# 18F_Proto2.net
KiCad netlist of a schematic drawn in EAGLE
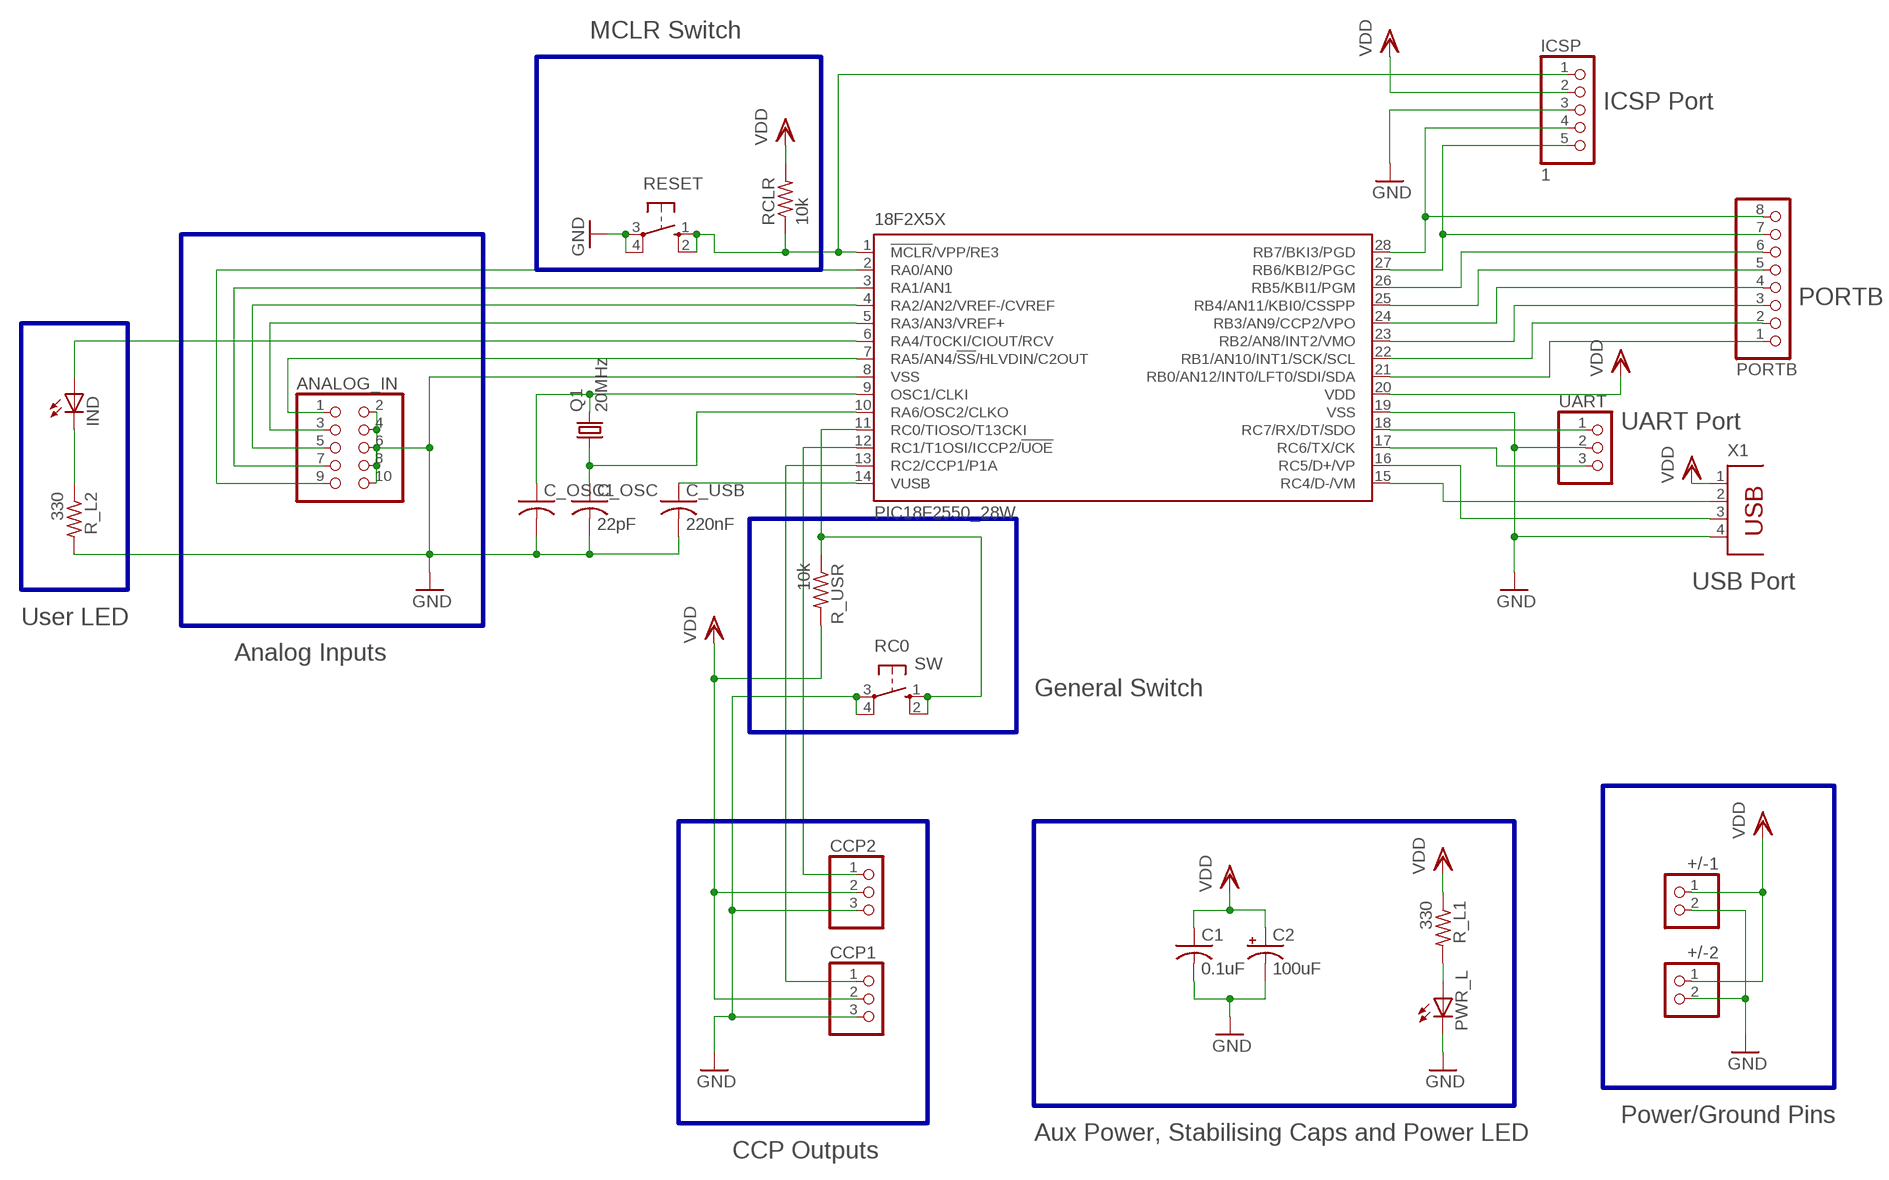
[diagram p0: schematic, sheet 1]

(export (version "E")
  (design (tool "Eeschema 10.0.6"))
  (components
    (comp (ref "+/-1")
      (value "PINHD-1X2")
      (footprint "eagle-import:1X02")
      (libsource (lib "eagle-import") (part "PINHD-1X2"))
    )
    (comp (ref "+/-2")
      (value "PINHD-1X2")
      (footprint "eagle-import:1X02")
      (libsource (lib "eagle-import") (part "PINHD-1X2"))
    )
    (comp (ref "18F2X5X")
      (value "PIC18F2550_28W")
      (footprint "eagle-import:SO28W")
      (fields (field (name "MF") "MICROCHIP") (field (name "MPN") "PIC18F2550-I/SO"))
      (libsource (lib "eagle-import") (part "PIC18F2_28W550"))
    )
    (comp (ref "ANALOG_IN")
      (value "PINHD-2X5")
      (footprint "eagle-import:2X05")
      (libsource (lib "eagle-import") (part "PINHD-2X5"))
    )
    (comp (ref "C1")
      (value "0.1uF")
      (footprint "eagle-import:C050-025X075")
      (libsource (lib "eagle-import") (part "C-US050-025X075"))
    )
    (comp (ref "C2")
      (value "100uF")
      (footprint "eagle-import:E2,5-6")
      (libsource (lib "eagle-import") (part "CPOL-USE2.5-6"))
    )
    (comp (ref "CCP1")
      (value "PINHD-1X3")
      (footprint "eagle-import:1X03")
      (libsource (lib "eagle-import") (part "PINHD-1X3"))
    )
    (comp (ref "CCP2")
      (value "PINHD-1X3")
      (footprint "eagle-import:1X03")
      (libsource (lib "eagle-import") (part "PINHD-1X3"))
    )
    (comp (ref "C_OSC")
      (value "22pF")
      (footprint "eagle-import:C025-025X050")
      (libsource (lib "eagle-import") (part "C-US025-025X050"))
    )
    (comp (ref "C_OSC1")
      (value "C-US025-025X050")
      (footprint "eagle-import:C025-025X050")
      (libsource (lib "eagle-import") (part "C-US025-025X050"))
    )
    (comp (ref "C_USB")
      (value "220nF")
      (footprint "eagle-import:C050-025X075")
      (libsource (lib "eagle-import") (part "C-US050-025X075"))
    )
    (comp (ref "ICSP")
      (value "1")
      (footprint "eagle-import:1X05")
      (libsource (lib "eagle-import") (part "PINHD-1X5"))
    )
    (comp (ref "IND")
      (value "LED3MM")
      (footprint "eagle-import:LED3MM")
      (libsource (lib "eagle-import") (part "LED3MM"))
    )
    (comp (ref "PORTB")
      (value "PINHD-1X8")
      (footprint "eagle-import:1X08")
      (libsource (lib "eagle-import") (part "PINHD-1X8"))
    )
    (comp (ref "PWR_L")
      (value "LED3MM")
      (footprint "eagle-import:LED3MM")
      (libsource (lib "eagle-import") (part "LED3MM"))
    )
    (comp (ref "Q1")
      (value "20MHz")
      (footprint "eagle-import:HC49_S")
      (libsource (lib "eagle-import") (part "CRYSTALHC49S"))
    )
    (comp (ref "RC0")
      (value "SW")
      (footprint "eagle-import:B3F-10XX")
      (fields (field (name "MPN") "B3F-1000"))
      (libsource (lib "eagle-import") (part "10-XX"))
    )
    (comp (ref "RCLR")
      (value "10k")
      (footprint "eagle-import:0204_7")
      (libsource (lib "eagle-import") (part "R-US_0204/7"))
    )
    (comp (ref "RESET")
      (value "10-XX")
      (footprint "eagle-import:B3F-10XX")
      (fields (field (name "MPN") "B3F-1000"))
      (libsource (lib "eagle-import") (part "10-XX"))
    )
    (comp (ref "R_L1")
      (value "330")
      (footprint "eagle-import:0204_7")
      (libsource (lib "eagle-import") (part "R-US_0204/7"))
    )
    (comp (ref "R_L2")
      (value "330")
      (footprint "eagle-import:0207_10")
      (libsource (lib "eagle-import") (part "R-US_0207/10"))
    )
    (comp (ref "R_USR")
      (value "10k")
      (footprint "eagle-import:0204_7")
      (libsource (lib "eagle-import") (part "R-US_0204/7"))
    )
    (comp (ref "UART")
      (value "PINHD-1X3")
      (footprint "eagle-import:1X03")
      (libsource (lib "eagle-import") (part "PINHD-1X3"))
    )
    (comp (ref "X1")
      (value "PN61729")
      (footprint "eagle-import:PN61729")
      (libsource (lib "eagle-import") (part "PN61729"))
    )
  )
  (nets
    (net (code "1") (name "GND") (class "Default")
      (node (ref "+/-1") (pin "2") (pinfunction "2_2") (pintype "passive"))
      (node (ref "+/-2") (pin "2") (pinfunction "2_2") (pintype "passive"))
      (node (ref "18F2X5X") (pin "19") (pinfunction "VSS_19") (pintype "power_in"))
      (node (ref "18F2X5X") (pin "8") (pinfunction "VSS_8") (pintype "power_in"))
      (node (ref "ANALOG_IN") (pin "10") (pinfunction "10_10") (pintype "passive"))
      (node (ref "ANALOG_IN") (pin "2") (pinfunction "2_2") (pintype "passive"))
      (node (ref "ANALOG_IN") (pin "4") (pinfunction "4_4") (pintype "passive"))
      (node (ref "ANALOG_IN") (pin "6") (pinfunction "6_6") (pintype "passive"))
      (node (ref "ANALOG_IN") (pin "8") (pinfunction "8_8") (pintype "passive"))
      (node (ref "C1") (pin "2") (pinfunction "2_2") (pintype "passive"))
      (node (ref "C2") (pin "-") (pinfunction "-_-") (pintype "passive"))
      (node (ref "CCP1") (pin "3") (pinfunction "3_3") (pintype "passive"))
      (node (ref "CCP2") (pin "3") (pinfunction "3_3") (pintype "passive"))
      (node (ref "C_OSC") (pin "2") (pinfunction "2_2") (pintype "passive"))
      (node (ref "C_OSC1") (pin "2") (pinfunction "2_2") (pintype "passive"))
      (node (ref "C_USB") (pin "2") (pinfunction "2_2") (pintype "passive"))
      (node (ref "ICSP") (pin "3") (pinfunction "3_3") (pintype "passive"))
      (node (ref "PWR_L") (pin "K") (pinfunction "C_K") (pintype "passive"))
      (node (ref "RC0") (pin "3") (pinfunction "P_3") (pintype "passive"))
      (node (ref "RC0") (pin "4") (pinfunction "P1_4") (pintype "passive"))
      (node (ref "RESET") (pin "3") (pinfunction "P_3") (pintype "passive"))
      (node (ref "RESET") (pin "4") (pinfunction "P1_4") (pintype "passive"))
      (node (ref "R_L2") (pin "2") (pinfunction "2_2") (pintype "passive"))
      (node (ref "UART") (pin "2") (pinfunction "2_2") (pintype "passive"))
      (node (ref "X1") (pin "4") (pinfunction "4_4") (pintype "passive"))
    )
    (net (code "2") (name "Net-(18F2X5X-OSC1{slash}CLKI)") (class "Default")
      (node (ref "18F2X5X") (pin "9") (pinfunction "OSC1/CLKI_9") (pintype "input"))
      (node (ref "C_OSC1") (pin "1") (pinfunction "1_1") (pintype "passive"))
      (node (ref "Q1") (pin "2") (pinfunction "2_2") (pintype "passive"))
    )
    (net (code "3") (name "Net-(18F2X5X-RA0{slash}AN0)") (class "Default")
      (node (ref "18F2X5X") (pin "2") (pinfunction "RA0/AN0_2") (pintype "bidirectional"))
      (node (ref "ANALOG_IN") (pin "9") (pinfunction "9_9") (pintype "passive"))
    )
    (net (code "4") (name "Net-(18F2X5X-RA1{slash}AN1)") (class "Default")
      (node (ref "18F2X5X") (pin "3") (pinfunction "RA1/AN1_3") (pintype "bidirectional"))
      (node (ref "ANALOG_IN") (pin "7") (pinfunction "7_7") (pintype "passive"))
    )
    (net (code "5") (name "Net-(18F2X5X-RA2{slash}AN2{slash}VREF-{slash}CVREF)") (class "Default")
      (node (ref "18F2X5X") (pin "4") (pinfunction "RA2/AN2/VREF-/CVREF_4") (pintype "bidirectional"))
      (node (ref "ANALOG_IN") (pin "5") (pinfunction "5_5") (pintype "passive"))
    )
    (net (code "6") (name "Net-(18F2X5X-RA3{slash}AN3{slash}VREF+)") (class "Default")
      (node (ref "18F2X5X") (pin "5") (pinfunction "RA3/AN3/VREF+_5") (pintype "bidirectional"))
      (node (ref "ANALOG_IN") (pin "3") (pinfunction "3_3") (pintype "passive"))
    )
    (net (code "7") (name "Net-(18F2X5X-RA4{slash}T0CKI{slash}CIOUT{slash}RCV)") (class "Default")
      (node (ref "18F2X5X") (pin "6") (pinfunction "RA4/T0CKI/CIOUT/RCV_6") (pintype "bidirectional"))
      (node (ref "IND") (pin "A") (pinfunction "A_A") (pintype "passive"))
    )
    (net (code "8") (name "Net-(18F2X5X-RA5{slash}AN4{slash}~{SS}{slash}HLVDIN{slash}C2OUT)") (class "Default")
      (node (ref "18F2X5X") (pin "7") (pinfunction "RA5/AN4/~{SS}/HLVDIN/C2OUT_7") (pintype "bidirectional"))
      (node (ref "ANALOG_IN") (pin "1") (pinfunction "1_1") (pintype "passive"))
    )
    (net (code "9") (name "Net-(18F2X5X-RA6{slash}OSC2{slash}CLKO)") (class "Default")
      (node (ref "18F2X5X") (pin "10") (pinfunction "RA6/OSC2/CLKO_10") (pintype "output"))
      (node (ref "C_OSC") (pin "1") (pinfunction "1_1") (pintype "passive"))
      (node (ref "Q1") (pin "1") (pinfunction "1_1") (pintype "passive"))
    )
    (net (code "10") (name "Net-(18F2X5X-RB0{slash}AN12{slash}INT0{slash}LFT0{slash}SDI{slash}SDA)") (class "Default")
      (node (ref "18F2X5X") (pin "21") (pinfunction "RB0/AN12/INT0/LFT0/SDI/SDA_21") (pintype "bidirectional"))
      (node (ref "PORTB") (pin "1") (pinfunction "1_1") (pintype "passive"))
    )
    (net (code "11") (name "Net-(18F2X5X-RB1{slash}AN10{slash}INT1{slash}SCK{slash}SCL)") (class "Default")
      (node (ref "18F2X5X") (pin "22") (pinfunction "RB1/AN10/INT1/SCK/SCL_22") (pintype "bidirectional"))
      (node (ref "PORTB") (pin "2") (pinfunction "2_2") (pintype "passive"))
    )
    (net (code "12") (name "Net-(18F2X5X-RB2{slash}AN8{slash}INT2{slash}VMO)") (class "Default")
      (node (ref "18F2X5X") (pin "23") (pinfunction "RB2/AN8/INT2/VMO_23") (pintype "bidirectional"))
      (node (ref "PORTB") (pin "3") (pinfunction "3_3") (pintype "passive"))
    )
    (net (code "13") (name "Net-(18F2X5X-RB3{slash}AN9{slash}CCP2{slash}VPO)") (class "Default")
      (node (ref "18F2X5X") (pin "24") (pinfunction "RB3/AN9/CCP2/VPO_24") (pintype "bidirectional"))
      (node (ref "PORTB") (pin "4") (pinfunction "4_4") (pintype "passive"))
    )
    (net (code "14") (name "Net-(18F2X5X-RB4{slash}AN11{slash}KBI0{slash}CSSPP)") (class "Default")
      (node (ref "18F2X5X") (pin "25") (pinfunction "RB4/AN11/KBI0/CSSPP_25") (pintype "bidirectional"))
      (node (ref "PORTB") (pin "5") (pinfunction "5_5") (pintype "passive"))
    )
    (net (code "15") (name "Net-(18F2X5X-RB5{slash}KBI1{slash}PGM)") (class "Default")
      (node (ref "18F2X5X") (pin "26") (pinfunction "RB5/KBI1/PGM_26") (pintype "bidirectional"))
      (node (ref "PORTB") (pin "6") (pinfunction "6_6") (pintype "passive"))
    )
    (net (code "16") (name "Net-(18F2X5X-RB6{slash}KBI2{slash}PGC)") (class "Default")
      (node (ref "18F2X5X") (pin "27") (pinfunction "RB6/KBI2/PGC_27") (pintype "bidirectional"))
      (node (ref "ICSP") (pin "5") (pinfunction "5_5") (pintype "passive"))
      (node (ref "PORTB") (pin "7") (pinfunction "7_7") (pintype "passive"))
    )
    (net (code "17") (name "Net-(18F2X5X-RB7{slash}BKI3{slash}PGD)") (class "Default")
      (node (ref "18F2X5X") (pin "28") (pinfunction "RB7/BKI3/PGD_28") (pintype "bidirectional"))
      (node (ref "ICSP") (pin "4") (pinfunction "4_4") (pintype "passive"))
      (node (ref "PORTB") (pin "8") (pinfunction "8_8") (pintype "passive"))
    )
    (net (code "18") (name "Net-(18F2X5X-RC0{slash}TIOSO{slash}T13CKI)") (class "Default")
      (node (ref "18F2X5X") (pin "11") (pinfunction "RC0/TIOSO/T13CKI_11") (pintype "bidirectional"))
      (node (ref "RC0") (pin "1") (pinfunction "S_1") (pintype "passive"))
      (node (ref "RC0") (pin "2") (pinfunction "S1_2") (pintype "passive"))
      (node (ref "R_USR") (pin "1") (pinfunction "1_1") (pintype "passive"))
    )
    (net (code "19") (name "Net-(18F2X5X-RC1{slash}T1OSI{slash}ICCP2{slash}~{UOE})") (class "Default")
      (node (ref "18F2X5X") (pin "12") (pinfunction "RC1/T1OSI/ICCP2/~{UOE}_12") (pintype "bidirectional"))
      (node (ref "CCP2") (pin "1") (pinfunction "1_1") (pintype "passive"))
    )
    (net (code "20") (name "Net-(18F2X5X-RC2{slash}CCP1{slash}P1A)") (class "Default")
      (node (ref "18F2X5X") (pin "13") (pinfunction "RC2/CCP1/P1A_13") (pintype "bidirectional"))
      (node (ref "CCP1") (pin "1") (pinfunction "1_1") (pintype "passive"))
    )
    (net (code "21") (name "Net-(18F2X5X-RC4{slash}D-{slash}VM)") (class "Default")
      (node (ref "18F2X5X") (pin "15") (pinfunction "RC4/D-/VM_15") (pintype "bidirectional"))
      (node (ref "X1") (pin "2") (pinfunction "2_2") (pintype "passive"))
    )
    (net (code "22") (name "Net-(18F2X5X-RC5{slash}D+{slash}VP)") (class "Default")
      (node (ref "18F2X5X") (pin "16") (pinfunction "RC5/D+/VP_16") (pintype "bidirectional"))
      (node (ref "X1") (pin "3") (pinfunction "3_3") (pintype "passive"))
    )
    (net (code "23") (name "Net-(18F2X5X-RC6{slash}TX{slash}CK)") (class "Default")
      (node (ref "18F2X5X") (pin "17") (pinfunction "RC6/TX/CK_17") (pintype "bidirectional"))
      (node (ref "UART") (pin "3") (pinfunction "3_3") (pintype "passive"))
    )
    (net (code "24") (name "Net-(18F2X5X-RC7{slash}RX{slash}DT{slash}SDO)") (class "Default")
      (node (ref "18F2X5X") (pin "18") (pinfunction "RC7/RX/DT/SDO_18") (pintype "bidirectional"))
      (node (ref "UART") (pin "1") (pinfunction "1_1") (pintype "passive"))
    )
    (net (code "25") (name "Net-(18F2X5X-VUSB)") (class "Default")
      (node (ref "18F2X5X") (pin "14") (pinfunction "VUSB_14") (pintype "bidirectional"))
      (node (ref "C_USB") (pin "1") (pinfunction "1_1") (pintype "passive"))
    )
    (net (code "26") (name "Net-(18F2X5X-~{MCLR}{slash}VPP{slash}RE3)") (class "Default")
      (node (ref "18F2X5X") (pin "1") (pinfunction "~{MCLR}/VPP/RE3_1") (pintype "input"))
      (node (ref "ICSP") (pin "1") (pinfunction "1_1") (pintype "passive"))
      (node (ref "RCLR") (pin "1") (pinfunction "1_1") (pintype "passive"))
      (node (ref "RESET") (pin "1") (pinfunction "S_1") (pintype "passive"))
      (node (ref "RESET") (pin "2") (pinfunction "S1_2") (pintype "passive"))
    )
    (net (code "27") (name "Net-(IND-C)") (class "Default")
      (node (ref "IND") (pin "K") (pinfunction "C_K") (pintype "passive"))
      (node (ref "R_L2") (pin "1") (pinfunction "1_1") (pintype "passive"))
    )
    (net (code "28") (name "Net-(PWR_L-PadA)") (class "Default")
      (node (ref "PWR_L") (pin "A") (pinfunction "A_A") (pintype "passive"))
      (node (ref "R_L1") (pin "2") (pinfunction "2_2") (pintype "passive"))
    )
    (net (code "29") (name "VDD") (class "Default")
      (node (ref "+/-1") (pin "1") (pinfunction "1_1") (pintype "passive"))
      (node (ref "+/-2") (pin "1") (pinfunction "1_1") (pintype "passive"))
      (node (ref "18F2X5X") (pin "20") (pinfunction "VDD_20") (pintype "power_in"))
      (node (ref "C1") (pin "1") (pinfunction "1_1") (pintype "passive"))
      (node (ref "C2") (pin "+") (pinfunction "+_+") (pintype "passive"))
      (node (ref "CCP1") (pin "2") (pinfunction "2_2") (pintype "passive"))
      (node (ref "CCP2") (pin "2") (pinfunction "2_2") (pintype "passive"))
      (node (ref "ICSP") (pin "2") (pinfunction "2_2") (pintype "passive"))
      (node (ref "RCLR") (pin "2") (pinfunction "2_2") (pintype "passive"))
      (node (ref "R_L1") (pin "1") (pinfunction "1_1") (pintype "passive"))
      (node (ref "R_USR") (pin "2") (pinfunction "2_2") (pintype "passive"))
      (node (ref "X1") (pin "1") (pinfunction "1_1") (pintype "passive"))
    )
  )
)
